# signal_in.net
KiCad netlist of a schematic drawn in Altium Designer
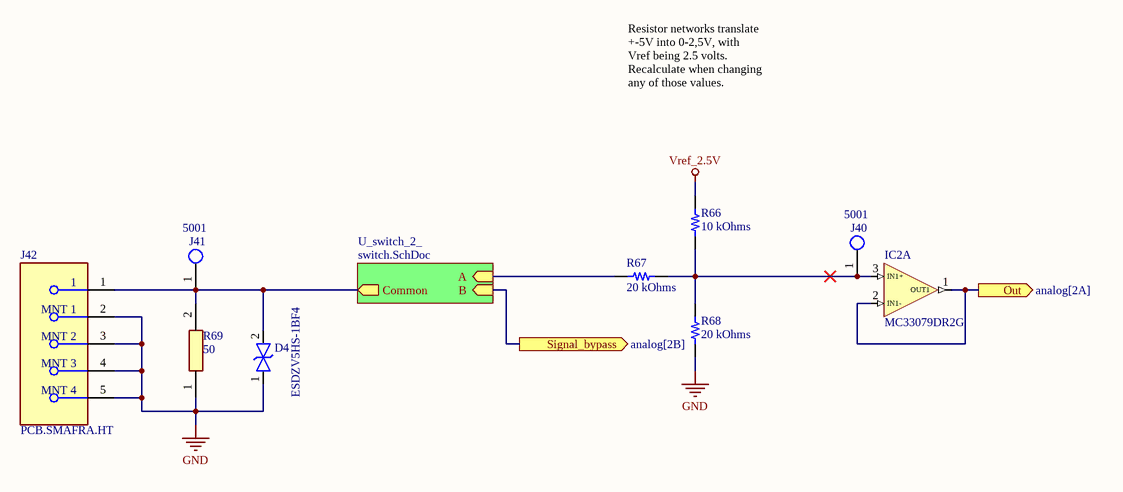
[diagram p0: signal_in.SchDoc]

(export (version "E")
  (design (tool "Eeschema 10.0.6"))
  (components
    (comp (ref "D4")
      (value "ESDZV5HS-1BF4")
      (footprint "ESDZV5HS1BF4")
      (description "TVS Diode (Bi-directional)")
      (fields (field (name "MOUSER PART NUMBER") "511-ESDZV5HS-1BF4"))
      (libsource (lib "za_koncar") (part "ESDZV5HS-1BF4"))
    )
    (comp (ref "IC2")
      (value "MC33079DR2G")
      (footprint "SOIC127P600X175-14N")
      (description "Integrated Circuit")
      (fields (field (name "MOUSER PART NUMBER") "863-MC33079DR2G"))
      (libsource (lib "za_koncar") (part "MC33079DR2G"))
    )
    (comp (ref "J40")
      (value "5001")
      (footprint "FP-5001-MFG")
      (description "PC TEST POINT MINIATURE BLACK")
      (libsource (lib "za_koncar") (part "CMP-2000-05181-2"))
    )
    (comp (ref "J41")
      (value "5001")
      (footprint "FP-5001-MFG")
      (description "PC TEST POINT MINIATURE BLACK")
      (libsource (lib "za_koncar") (part "CMP-2000-05181-2"))
    )
    (comp (ref "J42")
      (value "PCB.SMAFRA.HT")
      (footprint "FP-PCB_SMAFRA_HT-MFG")
      (description "CONN SMA JACK R/A 50OHM PCB")
      (libsource (lib "za_koncar") (part "CMP-111093-000003-1"))
    )
    (comp (ref "R66")
      (value "10 kOhms")
      (footprint "RES 1206_3216")
      (description "RES SMD 10K OHM 0.1% 1/4W 1206")
      (fields
        (field (name "PART NUMBER") "ERA-8AEB103V")
        (field (name "MANUFACTURER") "Panasonic Electronic Components")
      )
      (libsource (lib "Celestial Altium Library - altium_library") (part "Resistor"))
    )
    (comp (ref "R67")
      (value "20 kOhms")
      (footprint "RES 1206_3216")
      (description "RES SMD 20K OHM 0.1% 1/4W 1206")
      (fields
        (field (name "PART NUMBER") "ERA-8AEB203V")
        (field (name "MANUFACTURER") "Panasonic Electronic Components")
      )
      (libsource (lib "Celestial Altium Library - altium_library") (part "Resistor"))
    )
    (comp (ref "R68")
      (value "20 kOhms")
      (footprint "RES 1206_3216")
      (description "RES SMD 20K OHM 0.1% 1/4W 1206")
      (fields
        (field (name "PART NUMBER") "ERA-8AEB203V")
        (field (name "MANUFACTURER") "Panasonic Electronic Components")
      )
      (libsource (lib "Celestial Altium Library - altium_library") (part "Resistor"))
    )
    (comp (ref "R69")
      (value "50")
      (footprint "RESC6332X65N")
      (description "Resistor")
      (fields (field (name "MANUFACTURER_PART_NUMBER") "RNCL2512FT50R0"))
      (libsource (lib "za_koncar") (part "RNCL2512FT50R0"))
    )
  )
  (nets
    (net (code "1") (name "/A") (class "Default")
      (node (ref "R67") (pin "1") (pinfunction "1_1") (pintype "passive"))
    )
    (net (code "2") (name "/Common") (class "Default")
      (node (ref "D4") (pin "2") (pinfunction "2_2") (pintype "passive"))
      (node (ref "J41") (pin "1") (pinfunction "1_1") (pintype "passive"))
      (node (ref "J42") (pin "1") (pinfunction "1_1") (pintype "passive"))
      (node (ref "R69") (pin "2") (pinfunction "2_2") (pintype "passive"))
    )
    (net (code "3") (name "/Out") (class "Default")
      (node (ref "IC2") (pin "1") (pinfunction "OUT1_1") (pintype "output"))
      (node (ref "IC2") (pin "2") (pinfunction "IN1-_2") (pintype "input"))
    )
    (net (code "5") (name "GND") (class "Default")
      (node (ref "D4") (pin "1") (pinfunction "1_1") (pintype "passive"))
      (node (ref "J42") (pin "2") (pinfunction "MNT_1_2") (pintype "passive"))
      (node (ref "J42") (pin "3") (pinfunction "MNT_2_3") (pintype "passive"))
      (node (ref "J42") (pin "4") (pinfunction "MNT_3_4") (pintype "passive"))
      (node (ref "J42") (pin "5") (pinfunction "MNT_4_5") (pintype "passive"))
      (node (ref "R68") (pin "2") (pinfunction "2_2") (pintype "passive"))
      (node (ref "R69") (pin "1") (pinfunction "1_1") (pintype "passive"))
    )
    (net (code "6") (name "Net-(IC2A-IN1+)") (class "Default")
      (node (ref "IC2") (pin "3") (pinfunction "IN1+_3") (pintype "input"))
      (node (ref "J40") (pin "1") (pinfunction "1_1") (pintype "passive"))
      (node (ref "R66") (pin "2") (pinfunction "2_2") (pintype "passive"))
      (node (ref "R67") (pin "2") (pinfunction "2_2") (pintype "passive"))
      (node (ref "R68") (pin "1") (pinfunction "1_1") (pintype "passive"))
    )
    (net (code "7") (name "Vref_2.5V") (class "Default")
      (node (ref "R66") (pin "1") (pinfunction "1_1") (pintype "passive"))
    )
  )
)
